# booz_main.net
KiCad netlist of a schematic drawn in EAGLE
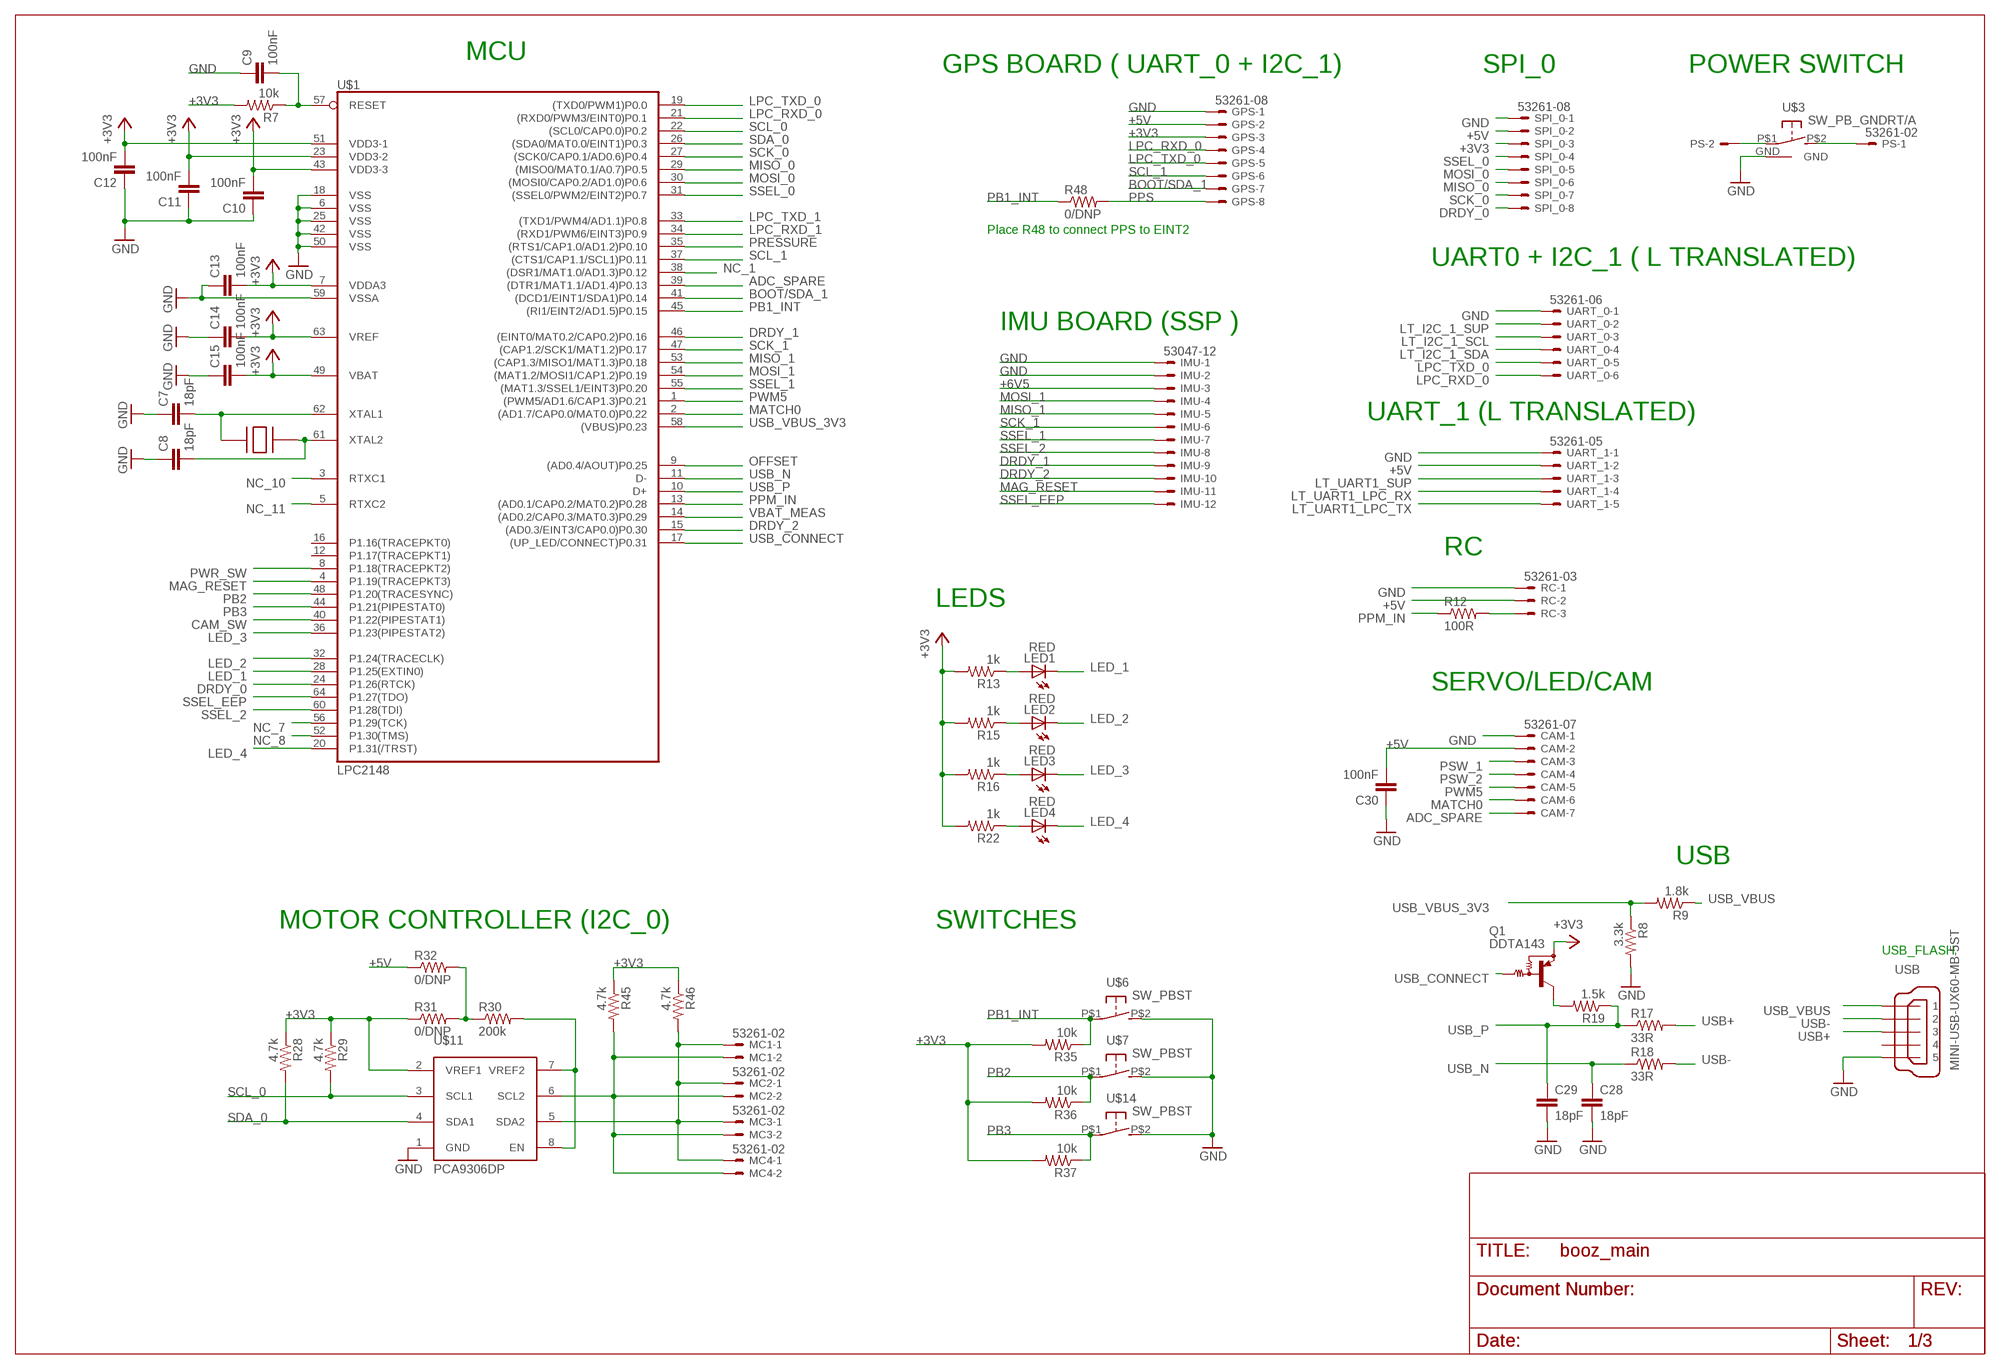
[diagram p0: schematic, sheet 1]
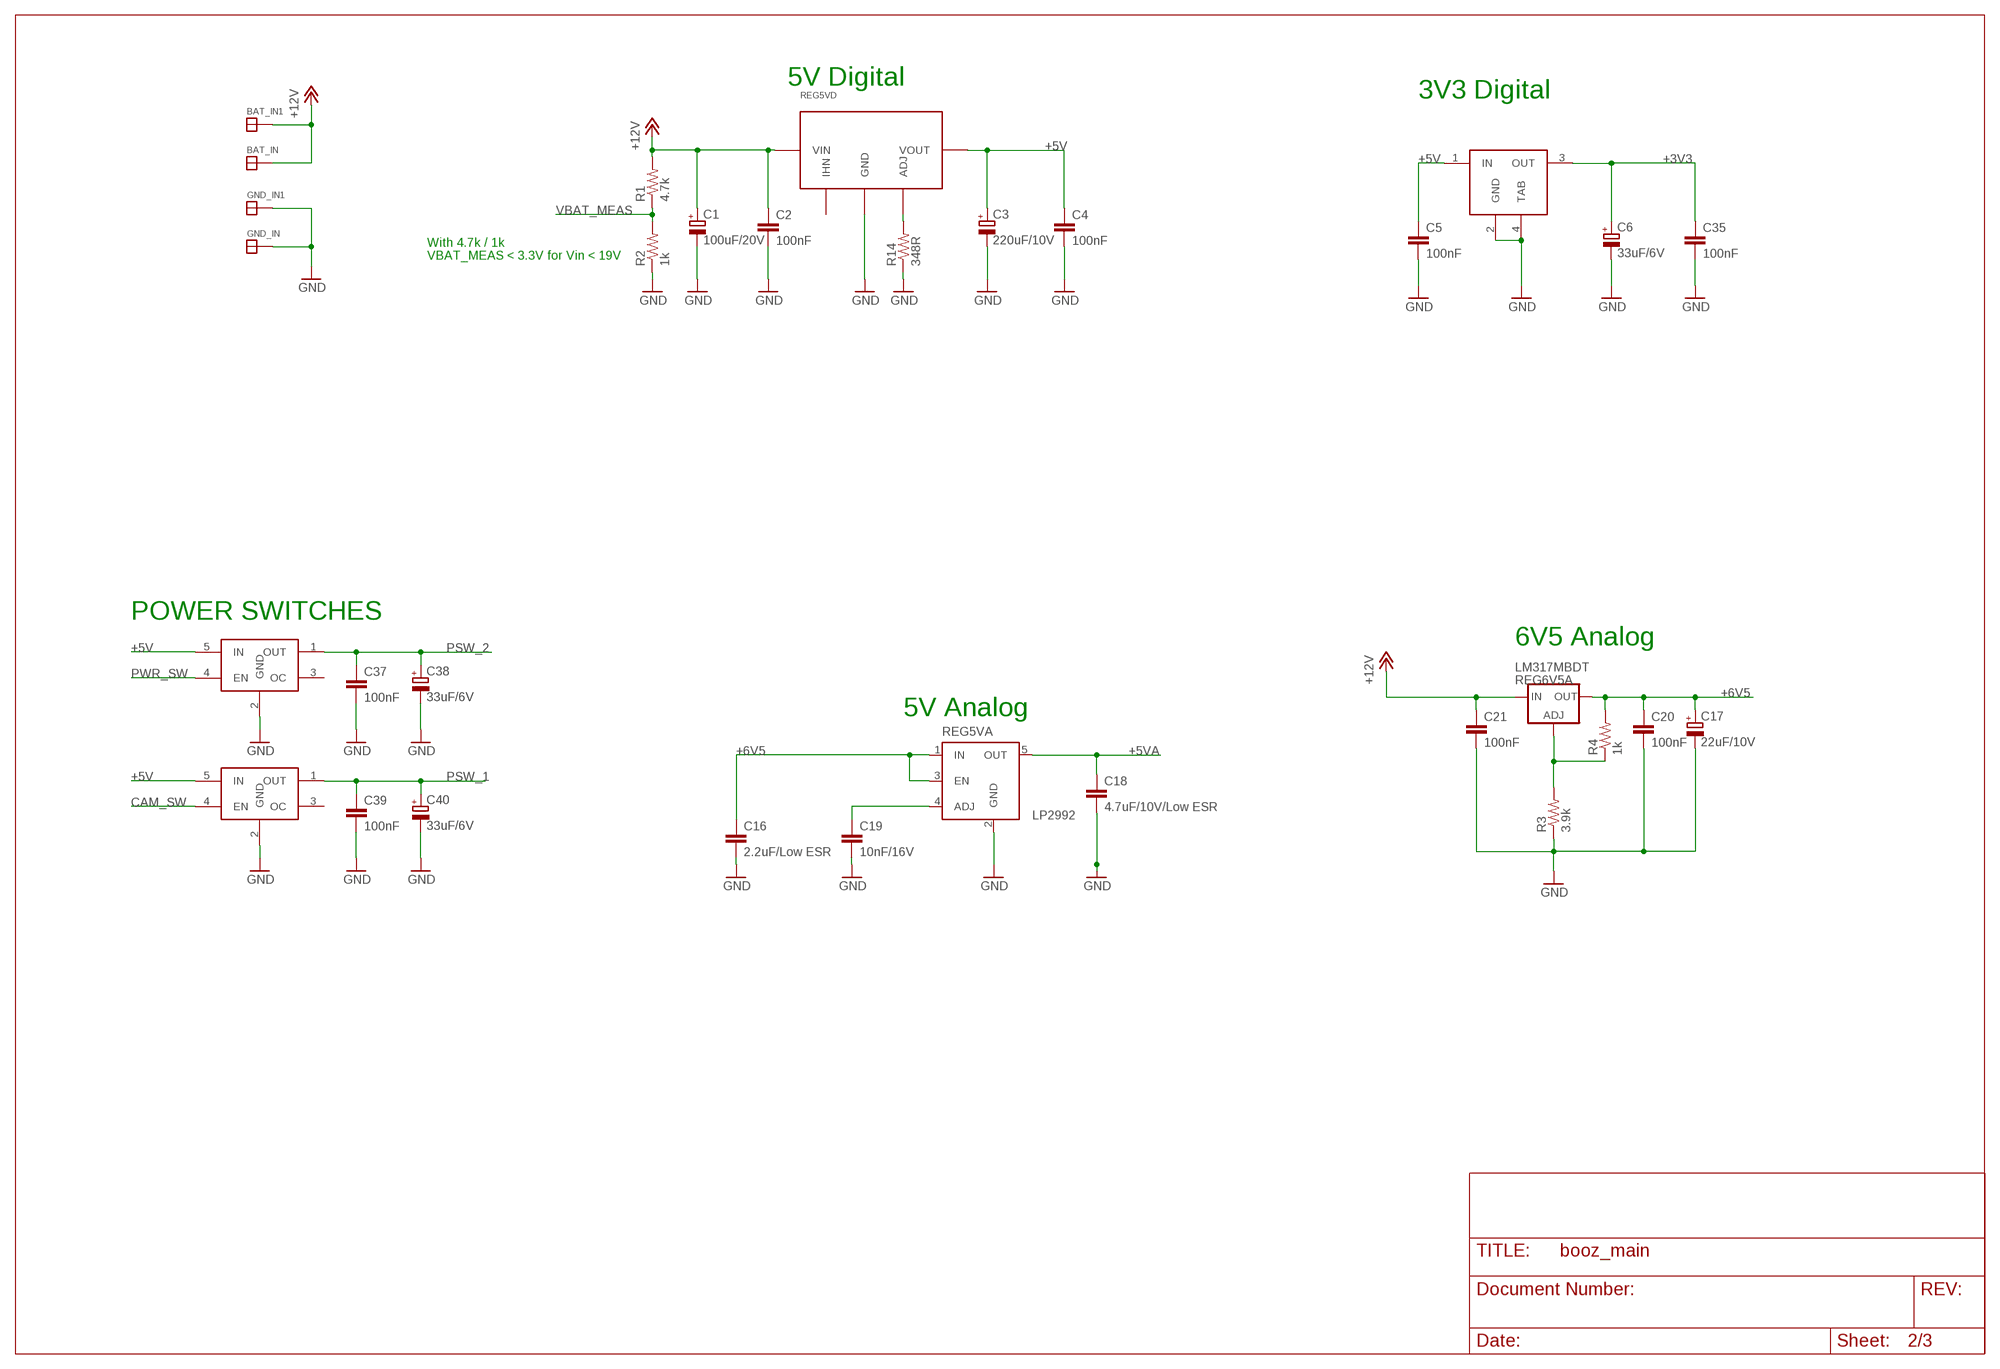
[diagram p1: schematic, sheet 2]
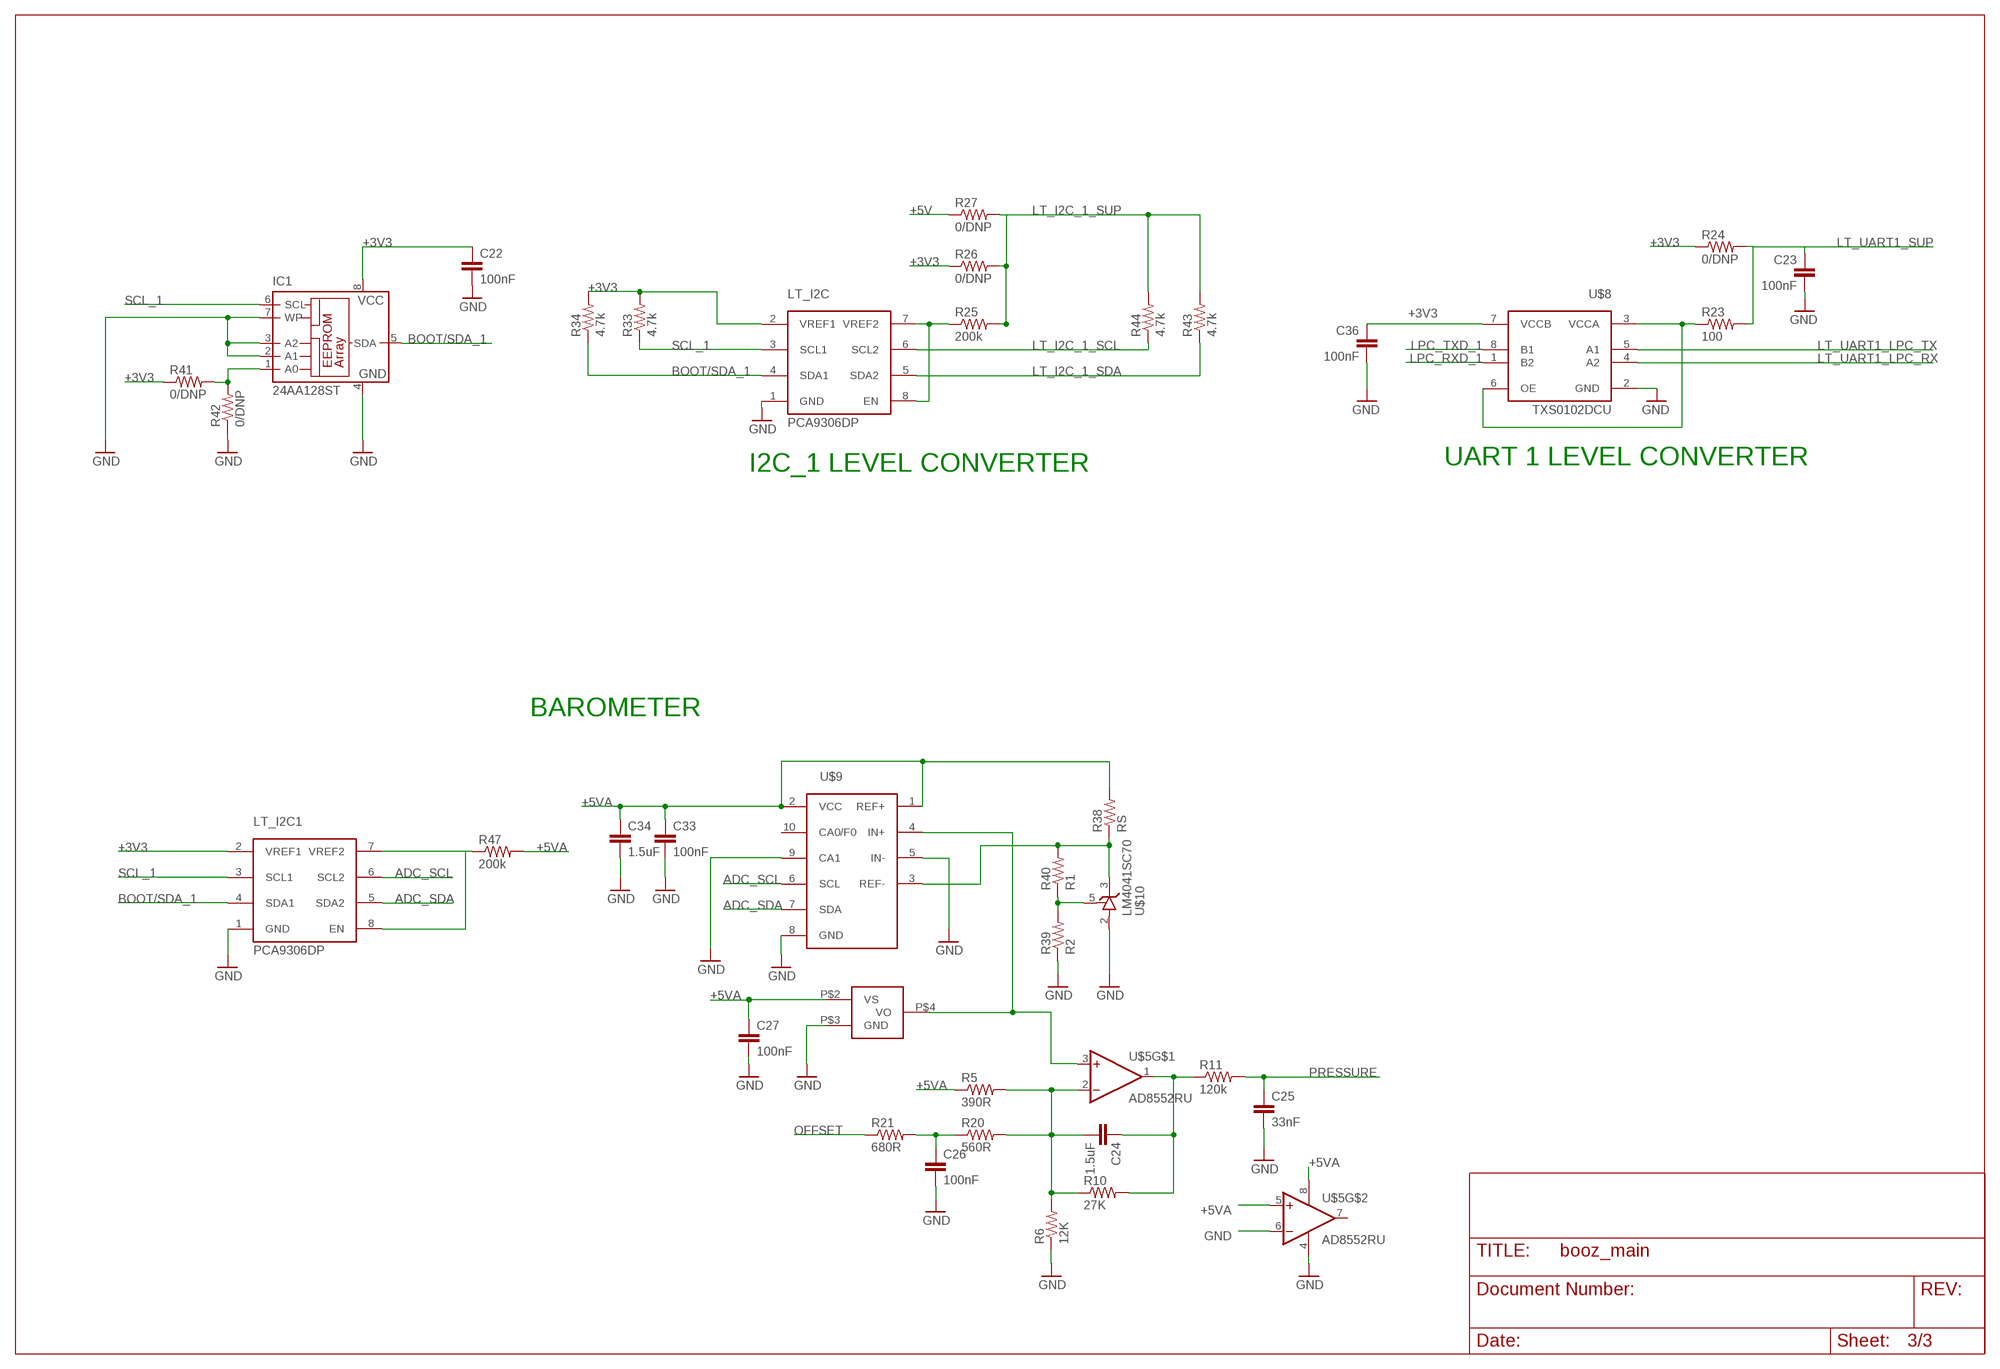
[diagram p2: schematic, sheet 3]

(export (version "E")
  (design (tool "Eeschema 10.0.6"))
  (components
    (comp (ref "C22")
      (value "100nF")
      (footprint "eagle-import:C0603")
      (libsource (lib "eagle-import") (part "C-EUC0603"))
    )
    (comp (ref "C23")
      (value "100nF")
      (footprint "eagle-import:C0603")
      (libsource (lib "eagle-import") (part "C-EUC0603"))
    )
    (comp (ref "C24")
      (value "1.5uF")
      (footprint "eagle-import:C0805")
      (libsource (lib "eagle-import") (part "C-EUC0805"))
    )
    (comp (ref "C25")
      (value "33nF")
      (footprint "eagle-import:C0805K")
      (libsource (lib "eagle-import") (part "C-EUC0805K"))
    )
    (comp (ref "C26")
      (value "100nF")
      (footprint "eagle-import:C0603")
      (libsource (lib "eagle-import") (part "C-EUC0603"))
    )
    (comp (ref "C27")
      (value "100nF")
      (footprint "eagle-import:C0603")
      (libsource (lib "eagle-import") (part "C-EUC0603"))
    )
    (comp (ref "C33")
      (value "100nF")
      (footprint "eagle-import:C0603")
      (libsource (lib "eagle-import") (part "C-EUC0603"))
    )
    (comp (ref "C34")
      (value "1.5uF")
      (footprint "eagle-import:C0805")
      (libsource (lib "eagle-import") (part "C-EUC0805"))
    )
    (comp (ref "C36")
      (value "100nF")
      (footprint "eagle-import:C0603")
      (libsource (lib "eagle-import") (part "C-EUC0603"))
    )
    (comp (ref "IC1")
      (value "24AA128ST")
      (footprint "eagle-import:TSSOP8")
      (libsource (lib "eagle-import") (part "24STAA128"))
    )
    (comp (ref "LT_I2C")
      (value "PCA9306DP")
      (footprint "eagle-import:TSSOP_B3")
      (libsource (lib "eagle-import") (part "PCA9306DP"))
    )
    (comp (ref "LT_I2C1")
      (value "PCA9306DP")
      (footprint "eagle-import:TSSOP_B3")
      (libsource (lib "eagle-import") (part "PCA9306DP"))
    )
    (comp (ref "R5")
      (value "390R")
      (footprint "eagle-import:R0603")
      (libsource (lib "eagle-import") (part "R-US_R0603"))
    )
    (comp (ref "R6")
      (value "12K")
      (footprint "eagle-import:R0603")
      (libsource (lib "eagle-import") (part "R-US_R0603"))
    )
    (comp (ref "R10")
      (value "27K")
      (footprint "eagle-import:R0603")
      (libsource (lib "eagle-import") (part "R-US_R0603"))
    )
    (comp (ref "R11")
      (value "120k")
      (footprint "eagle-import:R0603")
      (libsource (lib "eagle-import") (part "R-US_R0603"))
    )
    (comp (ref "R20")
      (value "560R")
      (footprint "eagle-import:R0603")
      (libsource (lib "eagle-import") (part "R-US_R0603"))
    )
    (comp (ref "R21")
      (value "680R")
      (footprint "eagle-import:R0603")
      (libsource (lib "eagle-import") (part "R-US_R0603"))
    )
    (comp (ref "R23")
      (value "100")
      (footprint "eagle-import:R0603")
      (libsource (lib "eagle-import") (part "R-US_R0603"))
    )
    (comp (ref "R24")
      (value "0/DNP")
      (footprint "eagle-import:R0603")
      (libsource (lib "eagle-import") (part "R-US_R0603"))
    )
    (comp (ref "R25")
      (value "200k")
      (footprint "eagle-import:R0603")
      (libsource (lib "eagle-import") (part "R-US_R0603"))
    )
    (comp (ref "R26")
      (value "0/DNP")
      (footprint "eagle-import:R0603")
      (libsource (lib "eagle-import") (part "R-US_R0603"))
    )
    (comp (ref "R27")
      (value "0/DNP")
      (footprint "eagle-import:R0603")
      (libsource (lib "eagle-import") (part "R-US_R0603"))
    )
    (comp (ref "R33")
      (value "4.7k")
      (footprint "eagle-import:R0603")
      (libsource (lib "eagle-import") (part "R-US_R0603"))
    )
    (comp (ref "R34")
      (value "4.7k")
      (footprint "eagle-import:R0603")
      (libsource (lib "eagle-import") (part "R-US_R0603"))
    )
    (comp (ref "R38")
      (value "RS")
      (footprint "eagle-import:R0603")
      (libsource (lib "eagle-import") (part "R-US_R0603"))
    )
    (comp (ref "R39")
      (value "R2")
      (footprint "eagle-import:R0603")
      (libsource (lib "eagle-import") (part "R-US_R0603"))
    )
    (comp (ref "R40")
      (value "R1")
      (footprint "eagle-import:R0603")
      (libsource (lib "eagle-import") (part "R-US_R0603"))
    )
    (comp (ref "R41")
      (value "0/DNP")
      (footprint "eagle-import:R0603")
      (libsource (lib "eagle-import") (part "R-US_R0603"))
    )
    (comp (ref "R42")
      (value "0/DNP")
      (footprint "eagle-import:R0603")
      (libsource (lib "eagle-import") (part "R-US_R0603"))
    )
    (comp (ref "R43")
      (value "4.7k")
      (footprint "eagle-import:R0603")
      (libsource (lib "eagle-import") (part "R-US_R0603"))
    )
    (comp (ref "R44")
      (value "4.7k")
      (footprint "eagle-import:R0603")
      (libsource (lib "eagle-import") (part "R-US_R0603"))
    )
    (comp (ref "R47")
      (value "200k")
      (footprint "eagle-import:R0603")
      (libsource (lib "eagle-import") (part "R-US_R0603"))
    )
    (comp (ref "U$2")
      (value "MPX6115")
      (footprint "eagle-import:CASE_1317")
      (libsource (lib "eagle-import") (part "MPX6115"))
    )
    (comp (ref "U$5")
      (value "AD8552RU")
      (footprint "eagle-import:TSSOP8")
      (libsource (lib "eagle-import") (part "AD8552RU"))
    )
    (comp (ref "U$8")
      (value "TXS0102DCU")
      (footprint "eagle-import:US8")
      (libsource (lib "eagle-import") (part "TXS0102DCU"))
    )
    (comp (ref "U$9")
      (value "LTC2485")
      (footprint "eagle-import:DFN10")
      (libsource (lib "eagle-import") (part "LTC2485"))
    )
    (comp (ref "U$10")
      (value "LM4041SC70")
      (footprint "eagle-import:SC70-5L")
      (libsource (lib "eagle-import") (part "LM4041SC70"))
    )
    (comp (ref "C7")
      (value "18pF")
      (footprint "eagle-import:C0603")
      (libsource (lib "eagle-import") (part "C-EUC0603"))
    )
    (comp (ref "C8")
      (value "18pF")
      (footprint "eagle-import:C0603")
      (libsource (lib "eagle-import") (part "C-EUC0603"))
    )
    (comp (ref "C9")
      (value "100nF")
      (footprint "eagle-import:C0603")
      (libsource (lib "eagle-import") (part "C-EUC0603"))
    )
    (comp (ref "C10")
      (value "100nF")
      (footprint "eagle-import:C0603")
      (libsource (lib "eagle-import") (part "C-EUC0603"))
    )
    (comp (ref "C11")
      (value "100nF")
      (footprint "eagle-import:C0603")
      (libsource (lib "eagle-import") (part "C-EUC0603"))
    )
    (comp (ref "C12")
      (value "100nF")
      (footprint "eagle-import:C0603")
      (libsource (lib "eagle-import") (part "C-EUC0603"))
    )
    (comp (ref "C13")
      (value "100nF")
      (footprint "eagle-import:C0603")
      (libsource (lib "eagle-import") (part "C-EUC0603"))
    )
    (comp (ref "C14")
      (value "100nF")
      (footprint "eagle-import:C0603")
      (libsource (lib "eagle-import") (part "C-EUC0603"))
    )
    (comp (ref "C15")
      (value "100nF")
      (footprint "eagle-import:C0603")
      (libsource (lib "eagle-import") (part "C-EUC0603"))
    )
    (comp (ref "C28")
      (value "18pF")
      (footprint "eagle-import:C0603")
      (libsource (lib "eagle-import") (part "C-EUC0603"))
    )
    (comp (ref "C29")
      (value "18pF")
      (footprint "eagle-import:C0603")
      (libsource (lib "eagle-import") (part "C-EUC0603"))
    )
    (comp (ref "C30")
      (value "100nF")
      (footprint "eagle-import:C0603")
      (libsource (lib "eagle-import") (part "C-EUC0603"))
    )
    (comp (ref "CAM")
      (value "53261-07")
      (footprint "eagle-import:53261-07")
      (libsource (lib "eagle-import") (part "53?-07261"))
    )
    (comp (ref "GPS")
      (value "53261-08")
      (footprint "eagle-import:53261-08")
      (libsource (lib "eagle-import") (part "53?-08261"))
    )
    (comp (ref "IMU")
      (value "53047-12")
      (footprint "eagle-import:53047-12")
      (libsource (lib "eagle-import") (part "53?-12047"))
    )
    (comp (ref "LED1")
      (value "RED")
      (footprint "eagle-import:CHIP-LED0805")
      (libsource (lib "eagle-import") (part "LEDCHIP-LED0805"))
    )
    (comp (ref "LED2")
      (value "RED")
      (footprint "eagle-import:CHIP-LED0805")
      (libsource (lib "eagle-import") (part "LEDCHIP-LED0805"))
    )
    (comp (ref "LED3")
      (value "RED")
      (footprint "eagle-import:CHIP-LED0805")
      (libsource (lib "eagle-import") (part "LEDCHIP-LED0805"))
    )
    (comp (ref "LED4")
      (value "RED")
      (footprint "eagle-import:CHIP-LED0805")
      (libsource (lib "eagle-import") (part "LEDCHIP-LED0805"))
    )
    (comp (ref "MC1")
      (value "53261-02")
      (footprint "eagle-import:53261-02")
      (libsource (lib "eagle-import") (part "53?-02261"))
    )
    (comp (ref "MC2")
      (value "53261-02")
      (footprint "eagle-import:53261-02")
      (libsource (lib "eagle-import") (part "53?-02261"))
    )
    (comp (ref "MC3")
      (value "53261-02")
      (footprint "eagle-import:53261-02")
      (libsource (lib "eagle-import") (part "53?-02261"))
    )
    (comp (ref "MC4")
      (value "53261-02")
      (footprint "eagle-import:53261-02")
      (libsource (lib "eagle-import") (part "53?-02261"))
    )
    (comp (ref "PS")
      (value "53261-02")
      (footprint "eagle-import:53261-02")
      (libsource (lib "eagle-import") (part "53?-02261"))
    )
    (comp (ref "Q1")
      (value "DDTA143")
      (footprint "eagle-import:SC59-BEC")
      (libsource (lib "eagle-import") (part "MUN2111T1"))
    )
    (comp (ref "R7")
      (value "10k")
      (footprint "eagle-import:R0603")
      (libsource (lib "eagle-import") (part "R-US_R0603"))
    )
    (comp (ref "R8")
      (value "3.3k")
      (footprint "eagle-import:R0603")
      (libsource (lib "eagle-import") (part "R-US_R0603"))
    )
    (comp (ref "R9")
      (value "1.8k")
      (footprint "eagle-import:R0603")
      (libsource (lib "eagle-import") (part "R-US_R0603"))
    )
    (comp (ref "R12")
      (value "100R")
      (footprint "eagle-import:R0603")
      (libsource (lib "eagle-import") (part "R-US_R0603"))
    )
    (comp (ref "R13")
      (value "1k")
      (footprint "eagle-import:R0603")
      (libsource (lib "eagle-import") (part "R-US_R0603"))
    )
    (comp (ref "R15")
      (value "1k")
      (footprint "eagle-import:R0603")
      (libsource (lib "eagle-import") (part "R-US_R0603"))
    )
    (comp (ref "R16")
      (value "1k")
      (footprint "eagle-import:R0603")
      (libsource (lib "eagle-import") (part "R-US_R0603"))
    )
    (comp (ref "R17")
      (value "33R")
      (footprint "eagle-import:R0603")
      (libsource (lib "eagle-import") (part "R-US_R0603"))
    )
    (comp (ref "R18")
      (value "33R")
      (footprint "eagle-import:R0603")
      (libsource (lib "eagle-import") (part "R-US_R0603"))
    )
    (comp (ref "R19")
      (value "1.5k")
      (footprint "eagle-import:R0603")
      (libsource (lib "eagle-import") (part "R-US_R0603"))
    )
    (comp (ref "R22")
      (value "1k")
      (footprint "eagle-import:R0603")
      (libsource (lib "eagle-import") (part "R-US_R0603"))
    )
    (comp (ref "R28")
      (value "4.7k")
      (footprint "eagle-import:R0603")
      (libsource (lib "eagle-import") (part "R-US_R0603"))
    )
    (comp (ref "R29")
      (value "4.7k")
      (footprint "eagle-import:R0603")
      (libsource (lib "eagle-import") (part "R-US_R0603"))
    )
    (comp (ref "R30")
      (value "200k")
      (footprint "eagle-import:R0603")
      (libsource (lib "eagle-import") (part "R-US_R0603"))
    )
    (comp (ref "R31")
      (value "0/DNP")
      (footprint "eagle-import:R0603")
      (libsource (lib "eagle-import") (part "R-US_R0603"))
    )
    (comp (ref "R32")
      (value "0/DNP")
      (footprint "eagle-import:R0603")
      (libsource (lib "eagle-import") (part "R-US_R0603"))
    )
    (comp (ref "R35")
      (value "10k")
      (footprint "eagle-import:R0603")
      (libsource (lib "eagle-import") (part "R-US_R0603"))
    )
    (comp (ref "R36")
      (value "10k")
      (footprint "eagle-import:R0603")
      (libsource (lib "eagle-import") (part "R-US_R0603"))
    )
    (comp (ref "R37")
      (value "10k")
      (footprint "eagle-import:R0603")
      (libsource (lib "eagle-import") (part "R-US_R0603"))
    )
    (comp (ref "R45")
      (value "4.7k")
      (footprint "eagle-import:R0603")
      (libsource (lib "eagle-import") (part "R-US_R0603"))
    )
    (comp (ref "R46")
      (value "4.7k")
      (footprint "eagle-import:R0603")
      (libsource (lib "eagle-import") (part "R-US_R0603"))
    )
    (comp (ref "R48")
      (value "0/DNP")
      (footprint "eagle-import:R0603")
      (libsource (lib "eagle-import") (part "R-US_R0603"))
    )
    (comp (ref "RC")
      (value "53261-03")
      (footprint "eagle-import:53261-03")
      (libsource (lib "eagle-import") (part "53?-03261"))
    )
    (comp (ref "SPI_0")
      (value "53261-08")
      (footprint "eagle-import:53261-08")
      (libsource (lib "eagle-import") (part "53?-08261"))
    )
    (comp (ref "U$1")
      (value "LPC2148")
      (footprint "eagle-import:SQFP-S-10X10-64")
      (libsource (lib "eagle-import") (part "LPC2148"))
    )
    (comp (ref "U$3")
      (value "SW_PB_GNDRT/A")
      (footprint "eagle-import:B3U-3100P")
      (libsource (lib "eagle-import") (part "SW_PB_GNDRT/A"))
    )
    (comp (ref "U$4")
      (value "CRYSTAL_CTS")
      (footprint "eagle-import:CTS_CRYSTAL")
      (libsource (lib "eagle-import") (part "CRYSTAL_CTS"))
    )
    (comp (ref "U$6")
      (value "SW_PBST")
      (footprint "eagle-import:B3U-1000P")
      (libsource (lib "eagle-import") (part "SW_PBST"))
    )
    (comp (ref "U$7")
      (value "SW_PBST")
      (footprint "eagle-import:B3U-1000P")
      (libsource (lib "eagle-import") (part "SW_PBST"))
    )
    (comp (ref "U$11")
      (value "PCA9306DP")
      (footprint "eagle-import:TSSOP_B3")
      (libsource (lib "eagle-import") (part "PCA9306DP"))
    )
    (comp (ref "U$14")
      (value "SW_PBST")
      (footprint "eagle-import:B3U-1000P")
      (libsource (lib "eagle-import") (part "SW_PBST"))
    )
    (comp (ref "UART_0")
      (value "53261-06")
      (footprint "eagle-import:53261-06")
      (libsource (lib "eagle-import") (part "53?-06261"))
    )
    (comp (ref "UART_1")
      (value "53261-05")
      (footprint "eagle-import:53261-05")
      (libsource (lib "eagle-import") (part "53?-05261"))
    )
    (comp (ref "USB")
      (value "MINI-USB-UX60-MB-5ST")
      (footprint "eagle-import:UX60-MB-5ST")
      (libsource (lib "eagle-import") (part "MINI-USB-UX60-MB-5ST"))
    )
    (comp (ref "BAT_IN")
      (value "SOLDER_PAD150_75")
      (footprint "eagle-import:SOLD_PAD_150_75")
      (libsource (lib "eagle-import") (part "SOLDER_PAD150_75"))
    )
    (comp (ref "BAT_IN1")
      (value "SOLDER_PAD150_75")
      (footprint "eagle-import:SOLD_PAD_150_75")
      (libsource (lib "eagle-import") (part "SOLDER_PAD150_75"))
    )
    (comp (ref "C1")
      (value "100uF/20V")
      (footprint "eagle-import:SMC_D")
      (libsource (lib "eagle-import") (part "CPOL-EUSMCD"))
    )
    (comp (ref "C2")
      (value "100nF")
      (footprint "eagle-import:C0603")
      (libsource (lib "eagle-import") (part "C-EUC0603"))
    )
    (comp (ref "C3")
      (value "220uF/10V")
      (footprint "eagle-import:SMC_D")
      (libsource (lib "eagle-import") (part "CPOL-EUSMCD"))
    )
    (comp (ref "C4")
      (value "100nF")
      (footprint "eagle-import:C0603")
      (libsource (lib "eagle-import") (part "C-EUC0603"))
    )
    (comp (ref "C5")
      (value "100nF")
      (footprint "eagle-import:C0603")
      (libsource (lib "eagle-import") (part "C-EUC0603"))
    )
    (comp (ref "C6")
      (value "33uF/6V")
      (footprint "eagle-import:CT3216")
      (libsource (lib "eagle-import") (part "CPOL-EUCT3216"))
    )
    (comp (ref "C16")
      (value "2.2uF/Low ESR")
      (footprint "eagle-import:C0603")
      (libsource (lib "eagle-import") (part "C-EUC0603"))
    )
    (comp (ref "C17")
      (value "22uF/10V")
      (footprint "eagle-import:CT3216")
      (libsource (lib "eagle-import") (part "CPOL-EUCT3216"))
    )
    (comp (ref "C18")
      (value "4.7uF/10V/Low ESR")
      (footprint "eagle-import:C0805K")
      (libsource (lib "eagle-import") (part "C-EUC0805K"))
    )
    (comp (ref "C19")
      (value "10nF/16V")
      (footprint "eagle-import:C0603K")
      (libsource (lib "eagle-import") (part "C-EUC0603K"))
    )
    (comp (ref "C20")
      (value "100nF")
      (footprint "eagle-import:C0603")
      (libsource (lib "eagle-import") (part "C-EUC0603"))
    )
    (comp (ref "C21")
      (value "100nF")
      (footprint "eagle-import:C0603")
      (libsource (lib "eagle-import") (part "C-EUC0603"))
    )
    (comp (ref "C35")
      (value "100nF")
      (footprint "eagle-import:C0603")
      (libsource (lib "eagle-import") (part "C-EUC0603"))
    )
    (comp (ref "C37")
      (value "100nF")
      (footprint "eagle-import:C0603")
      (libsource (lib "eagle-import") (part "C-EUC0603"))
    )
    (comp (ref "C38")
      (value "33uF/6V")
      (footprint "eagle-import:CT3216")
      (libsource (lib "eagle-import") (part "CPOL-EUCT3216"))
    )
    (comp (ref "C39")
      (value "100nF")
      (footprint "eagle-import:C0603")
      (libsource (lib "eagle-import") (part "C-EUC0603"))
    )
    (comp (ref "C40")
      (value "33uF/6V")
      (footprint "eagle-import:CT3216")
      (libsource (lib "eagle-import") (part "CPOL-EUCT3216"))
    )
    (comp (ref "GND_IN")
      (value "SOLDER_PAD150_75")
      (footprint "eagle-import:SOLD_PAD_150_75")
      (libsource (lib "eagle-import") (part "SOLDER_PAD150_75"))
    )
    (comp (ref "GND_IN1")
      (value "SOLDER_PAD150_75")
      (footprint "eagle-import:SOLD_PAD_150_75")
      (libsource (lib "eagle-import") (part "SOLDER_PAD150_75"))
    )
    (comp (ref "R1")
      (value "4.7k")
      (footprint "eagle-import:R0603")
      (libsource (lib "eagle-import") (part "R-US_R0603"))
    )
    (comp (ref "R2")
      (value "1k")
      (footprint "eagle-import:R0603")
      (libsource (lib "eagle-import") (part "R-US_R0603"))
    )
    (comp (ref "R3")
      (value "3.9k")
      (footprint "eagle-import:R0603")
      (libsource (lib "eagle-import") (part "R-US_R0603"))
    )
    (comp (ref "R4")
      (value "1k")
      (footprint "eagle-import:R0603")
      (libsource (lib "eagle-import") (part "R-US_R0603"))
    )
    (comp (ref "R14")
      (value "348R")
      (footprint "eagle-import:R0603")
      (libsource (lib "eagle-import") (part "R-US_R0603"))
    )
    (comp (ref "REG3V3D")
      (value "LM3940IMP-3.3")
      (footprint "eagle-import:SOT223-R")
      (libsource (lib "eagle-import") (part "LM3940IMP-3.3"))
    )
    (comp (ref "REG5VA")
      (value "LP2992")
      (footprint "eagle-import:SOT23-5")
      (libsource (lib "eagle-import") (part "MIC5219BM5"))
    )
    (comp (ref "REG5VD")
      (value "PTHTH")
      (footprint "eagle-import:PTH_TH")
      (libsource (lib "eagle-import") (part "PTHTH"))
    )
    (comp (ref "REG6V5A")
      (value "LM317MBDT")
      (footprint "eagle-import:DPACK")
      (libsource (lib "eagle-import") (part "LM317?MBDT"))
    )
    (comp (ref "U$12")
      (value "TPS2051B")
      (footprint "eagle-import:SOT23-5L")
      (libsource (lib "eagle-import") (part "TPS2051B"))
    )
    (comp (ref "U$13")
      (value "TPS2051B")
      (footprint "eagle-import:SOT23-5L")
      (libsource (lib "eagle-import") (part "TPS2051B"))
    )
  )
  (nets
    (net (code "1") (name "+3V3") (class "Default")
      (node (ref "C10") (pin "2") (pinfunction "2_2") (pintype "passive"))
      (node (ref "C11") (pin "2") (pinfunction "2_2") (pintype "passive"))
      (node (ref "C12") (pin "2") (pinfunction "2_2") (pintype "passive"))
      (node (ref "C13") (pin "2") (pinfunction "2_2") (pintype "passive"))
      (node (ref "C14") (pin "2") (pinfunction "2_2") (pintype "passive"))
      (node (ref "C15") (pin "2") (pinfunction "2_2") (pintype "passive"))
      (node (ref "C22") (pin "1") (pinfunction "1_1") (pintype "passive"))
      (node (ref "C35") (pin "1") (pinfunction "1_1") (pintype "passive"))
      (node (ref "C36") (pin "1") (pinfunction "1_1") (pintype "passive"))
      (node (ref "C6") (pin "+") (pinfunction "+_+") (pintype "passive"))
      (node (ref "GPS") (pin "3") (pinfunction "S_3") (pintype "passive"))
      (node (ref "IC1") (pin "8") (pinfunction "VCC_8") (pintype "power_in"))
      (node (ref "LT_I2C") (pin "2") (pinfunction "VREF1_2") (pintype "bidirectional"))
      (node (ref "LT_I2C1") (pin "2") (pinfunction "VREF1_2") (pintype "bidirectional"))
      (node (ref "Q1") (pin "E") (pinfunction "E_E") (pintype "passive"))
      (node (ref "R13") (pin "2") (pinfunction "2_2") (pintype "passive"))
      (node (ref "R15") (pin "2") (pinfunction "2_2") (pintype "passive"))
      (node (ref "R16") (pin "2") (pinfunction "2_2") (pintype "passive"))
      (node (ref "R22") (pin "2") (pinfunction "2_2") (pintype "passive"))
      (node (ref "R24") (pin "1") (pinfunction "1_1") (pintype "passive"))
      (node (ref "R26") (pin "1") (pinfunction "1_1") (pintype "passive"))
      (node (ref "R28") (pin "1") (pinfunction "1_1") (pintype "passive"))
      (node (ref "R29") (pin "1") (pinfunction "1_1") (pintype "passive"))
      (node (ref "R31") (pin "1") (pinfunction "1_1") (pintype "passive"))
      (node (ref "R33") (pin "2") (pinfunction "2_2") (pintype "passive"))
      (node (ref "R34") (pin "2") (pinfunction "2_2") (pintype "passive"))
      (node (ref "R35") (pin "2") (pinfunction "2_2") (pintype "passive"))
      (node (ref "R36") (pin "2") (pinfunction "2_2") (pintype "passive"))
      (node (ref "R37") (pin "2") (pinfunction "2_2") (pintype "passive"))
      (node (ref "R41") (pin "1") (pinfunction "1_1") (pintype "passive"))
      (node (ref "R45") (pin "1") (pinfunction "1_1") (pintype "passive"))
      (node (ref "R46") (pin "1") (pinfunction "1_1") (pintype "passive"))
      (node (ref "R7") (pin "2") (pinfunction "2_2") (pintype "passive"))
      (node (ref "REG3V3D") (pin "3") (pinfunction "OUT_3") (pintype "bidirectional"))
      (node (ref "SPI_0") (pin "3") (pinfunction "S_3") (pintype "passive"))
      (node (ref "U$1") (pin "23") (pinfunction "VDD3-2_23") (pintype "power_in"))
      (node (ref "U$1") (pin "43") (pinfunction "VDD3-3_43") (pintype "power_in"))
      (node (ref "U$1") (pin "49") (pinfunction "VBAT_49") (pintype "power_in"))
      (node (ref "U$1") (pin "51") (pinfunction "VDD3-1_51") (pintype "power_in"))
      (node (ref "U$1") (pin "63") (pinfunction "VREF_63") (pintype "input"))
      (node (ref "U$1") (pin "7") (pinfunction "VDDA3_7") (pintype "power_in"))
      (node (ref "U$11") (pin "2") (pinfunction "VREF1_2") (pintype "bidirectional"))
      (node (ref "U$8") (pin "7") (pinfunction "VCCB_7") (pintype "bidirectional"))
    )
    (net (code "2") (name "+5V") (class "Default")
      (node (ref "C3") (pin "+") (pinfunction "+_+") (pintype "passive"))
      (node (ref "C30") (pin "2") (pinfunction "2_2") (pintype "passive"))
      (node (ref "C4") (pin "1") (pinfunction "1_1") (pintype "passive"))
      (node (ref "C5") (pin "1") (pinfunction "1_1") (pintype "passive"))
      (node (ref "CAM") (pin "2") (pinfunction "S_2") (pintype "passive"))
      (node (ref "GPS") (pin "2") (pinfunction "S_2") (pintype "passive"))
      (node (ref "R27") (pin "1") (pinfunction "1_1") (pintype "passive"))
      (node (ref "R32") (pin "1") (pinfunction "1_1") (pintype "passive"))
      (node (ref "RC") (pin "2") (pinfunction "S_2") (pintype "passive"))
      (node (ref "REG3V3D") (pin "1") (pinfunction "IN_1") (pintype "bidirectional"))
      (node (ref "REG5VD") (pin "P$3") (pinfunction "VOUT_P$3") (pintype "bidirectional"))
      (node (ref "SPI_0") (pin "2") (pinfunction "S_2") (pintype "passive"))
      (node (ref "U$12") (pin "5") (pinfunction "IN_5") (pintype "bidirectional"))
      (node (ref "U$13") (pin "5") (pinfunction "IN_5") (pintype "bidirectional"))
      (node (ref "UART_1") (pin "2") (pinfunction "S_2") (pintype "passive"))
    )
    (net (code "3") (name "+5VA") (class "Default")
      (node (ref "C18") (pin "1") (pinfunction "1_1") (pintype "passive"))
      (node (ref "C27") (pin "1") (pinfunction "1_1") (pintype "passive"))
      (node (ref "C33") (pin "1") (pinfunction "1_1") (pintype "passive"))
      (node (ref "C34") (pin "1") (pinfunction "1_1") (pintype "passive"))
      (node (ref "R38") (pin "2") (pinfunction "2_2") (pintype "passive"))
      (node (ref "R47") (pin "2") (pinfunction "2_2") (pintype "passive"))
      (node (ref "R5") (pin "1") (pinfunction "1_1") (pintype "passive"))
      (node (ref "REG5VA") (pin "5") (pinfunction "OUT_5") (pintype "output"))
      (node (ref "U$2") (pin "P$2") (pinfunction "VS_P$2") (pintype "bidirectional"))
      (node (ref "U$5") (pin "5") (pinfunction "+IN_5") (pintype "input"))
      (node (ref "U$5") (pin "8") (pinfunction "V+_8") (pintype "power_in"))
      (node (ref "U$9") (pin "1") (pinfunction "REF+_1") (pintype "bidirectional"))
      (node (ref "U$9") (pin "2") (pinfunction "VCC_2") (pintype "bidirectional"))
    )
    (net (code "4") (name "+6V5") (class "Default")
      (node (ref "C16") (pin "1") (pinfunction "1_1") (pintype "passive"))
      (node (ref "C17") (pin "+") (pinfunction "+_+") (pintype "passive"))
      (node (ref "C20") (pin "1") (pinfunction "1_1") (pintype "passive"))
      (node (ref "IMU") (pin "3") (pinfunction "S_3") (pintype "passive"))
      (node (ref "R4") (pin "2") (pinfunction "2_2") (pintype "passive"))
      (node (ref "REG5VA") (pin "1") (pinfunction "IN_1") (pintype "input"))
      (node (ref "REG5VA") (pin "3") (pinfunction "EN_3") (pintype "input"))
      (node (ref "REG6V5A") (pin "4") (pinfunction "OUT_4") (pintype "passive"))
    )
    (net (code "5") (name "+12V") (class "Default")
      (node (ref "BAT_IN") (pin "P$1") (pinfunction "P$1_P$1") (pintype "bidirectional"))
      (node (ref "BAT_IN1") (pin "P$1") (pinfunction "P$1_P$1") (pintype "bidirectional"))
      (node (ref "C1") (pin "+") (pinfunction "+_+") (pintype "passive"))
      (node (ref "C2") (pin "1") (pinfunction "1_1") (pintype "passive"))
      (node (ref "C21") (pin "1") (pinfunction "1_1") (pintype "passive"))
      (node (ref "R1") (pin "2") (pinfunction "2_2") (pintype "passive"))
      (node (ref "REG5VD") (pin "P$1") (pinfunction "VIN_P$1") (pintype "bidirectional"))
      (node (ref "REG6V5A") (pin "3") (pinfunction "IN_3") (pintype "input"))
    )
    (net (code "6") (name "ADC_SCL") (class "Default")
      (node (ref "LT_I2C1") (pin "6") (pinfunction "SCL2_6") (pintype "bidirectional"))
      (node (ref "U$9") (pin "6") (pinfunction "SCL_6") (pintype "bidirectional"))
    )
    (net (code "7") (name "ADC_SDA") (class "Default")
      (node (ref "LT_I2C1") (pin "5") (pinfunction "SDA2_5") (pintype "bidirectional"))
      (node (ref "U$9") (pin "7") (pinfunction "SDA_7") (pintype "bidirectional"))
    )
    (net (code "8") (name "ADC_SPARE") (class "Default")
      (node (ref "CAM") (pin "7") (pinfunction "S_7") (pintype "passive"))
      (node (ref "U$1") (pin "39") (pinfunction "(DTR1/MAT1.1/AD1.4)P0.13_39") (pintype "bidirectional"))
    )
    (net (code "9") (name "BOOT{slash}SDA_1") (class "Default")
      (node (ref "GPS") (pin "7") (pinfunction "S_7") (pintype "passive"))
      (node (ref "IC1") (pin "5") (pinfunction "SDA_5") (pintype "bidirectional"))
      (node (ref "LT_I2C") (pin "4") (pinfunction "SDA1_4") (pintype "bidirectional"))
      (node (ref "LT_I2C1") (pin "4") (pinfunction "SDA1_4") (pintype "bidirectional"))
      (node (ref "R34") (pin "1") (pinfunction "1_1") (pintype "passive"))
      (node (ref "U$1") (pin "41") (pinfunction "(DCD1/EINT1/SDA1)P0.14_41") (pintype "bidirectional"))
    )
    (net (code "10") (name "CAM_SW") (class "Default")
      (node (ref "U$1") (pin "40") (pinfunction "P1.22(PIPESTAT1)_40") (pintype "bidirectional"))
      (node (ref "U$13") (pin "4") (pinfunction "EN_4") (pintype "bidirectional"))
    )
    (net (code "11") (name "DRDY_0") (class "Default")
      (node (ref "SPI_0") (pin "8") (pinfunction "S_8") (pintype "passive"))
      (node (ref "U$1") (pin "24") (pinfunction "P1.26(RTCK)_24") (pintype "bidirectional"))
    )
    (net (code "12") (name "DRDY_1") (class "Default")
      (node (ref "IMU") (pin "9") (pinfunction "S_9") (pintype "passive"))
      (node (ref "U$1") (pin "46") (pinfunction "(EINT0/MAT0.2/CAP0.2)P0.16_46") (pintype "bidirectional"))
    )
    (net (code "13") (name "DRDY_2") (class "Default")
      (node (ref "IMU") (pin "10") (pinfunction "S_10") (pintype "passive"))
      (node (ref "U$1") (pin "15") (pinfunction "(AD0.3/EINT3/CAP0.0)P0.30_15") (pintype "bidirectional"))
    )
    (net (code "14") (name "GND") (class "Default")
      (node (ref "C1") (pin "-") (pinfunction "-_-") (pintype "passive"))
      (node (ref "C10") (pin "1") (pinfunction "1_1") (pintype "passive"))
      (node (ref "C11") (pin "1") (pinfunction "1_1") (pintype "passive"))
      (node (ref "C12") (pin "1") (pinfunction "1_1") (pintype "passive"))
      (node (ref "C13") (pin "1") (pinfunction "1_1") (pintype "passive"))
      (node (ref "C14") (pin "1") (pinfunction "1_1") (pintype "passive"))
      (node (ref "C15") (pin "1") (pinfunction "1_1") (pintype "passive"))
      (node (ref "C16") (pin "2") (pinfunction "2_2") (pintype "passive"))
      (node (ref "C17") (pin "-") (pinfunction "-_-") (pintype "passive"))
      (node (ref "C18") (pin "2") (pinfunction "2_2") (pintype "passive"))
      (node (ref "C19") (pin "2") (pinfunction "2_2") (pintype "passive"))
      (node (ref "C2") (pin "2") (pinfunction "2_2") (pintype "passive"))
      (node (ref "C20") (pin "2") (pinfunction "2_2") (pintype "passive"))
      (node (ref "C21") (pin "2") (pinfunction "2_2") (pintype "passive"))
      (node (ref "C22") (pin "2") (pinfunction "2_2") (pintype "passive"))
      (node (ref "C23") (pin "2") (pinfunction "2_2") (pintype "passive"))
      (node (ref "C25") (pin "2") (pinfunction "2_2") (pintype "passive"))
      (node (ref "C26") (pin "2") (pinfunction "2_2") (pintype "passive"))
      (node (ref "C27") (pin "2") (pinfunction "2_2") (pintype "passive"))
      (node (ref "C28") (pin "2") (pinfunction "2_2") (pintype "passive"))
      (node (ref "C29") (pin "2") (pinfunction "2_2") (pintype "passive"))
      (node (ref "C3") (pin "-") (pinfunction "-_-") (pintype "passive"))
      (node (ref "C30") (pin "1") (pinfunction "1_1") (pintype "passive"))
      (node (ref "C33") (pin "2") (pinfunction "2_2") (pintype "passive"))
      (node (ref "C34") (pin "2") (pinfunction "2_2") (pintype "passive"))
      (node (ref "C35") (pin "2") (pinfunction "2_2") (pintype "passive"))
      (node (ref "C36") (pin "2") (pinfunction "2_2") (pintype "passive"))
      (node (ref "C37") (pin "2") (pinfunction "2_2") (pintype "passive"))
      (node (ref "C38") (pin "-") (pinfunction "-_-") (pintype "passive"))
      (node (ref "C39") (pin "2") (pinfunction "2_2") (pintype "passive"))
      (node (ref "C4") (pin "2") (pinfunction "2_2") (pintype "passive"))
      (node (ref "C40") (pin "-") (pinfunction "-_-") (pintype "passive"))
      (node (ref "C5") (pin "2") (pinfunction "2_2") (pintype "passive"))
      (node (ref "C6") (pin "-") (pinfunction "-_-") (pintype "passive"))
      (node (ref "C7") (pin "1") (pinfunction "1_1") (pintype "passive"))
      (node (ref "C8") (pin "1") (pinfunction "1_1") (pintype "passive"))
      (node (ref "C9") (pin "1") (pinfunction "1_1") (pintype "passive"))
      (node (ref "CAM") (pin "1") (pinfunction "S_1") (pintype "passive"))
      (node (ref "GND_IN") (pin "P$1") (pinfunction "P$1_P$1") (pintype "bidirectional"))
      (node (ref "GND_IN1") (pin "P$1") (pinfunction "P$1_P$1") (pintype "bidirectional"))
      (node (ref "GPS") (pin "1") (pinfunction "S_1") (pintype "passive"))
      (node (ref "IC1") (pin "2") (pinfunction "A1_2") (pintype "input"))
      (node (ref "IC1") (pin "3") (pinfunction "A2_3") (pintype "input"))
      (node (ref "IC1") (pin "4") (pinfunction "GND_4") (pintype "power_in"))
      (node (ref "IC1") (pin "7") (pinfunction "WP_7") (pintype "input"))
      (node (ref "IMU") (pin "1") (pinfunction "S_1") (pintype "passive"))
      (node (ref "IMU") (pin "2") (pinfunction "S_2") (pintype "passive"))
      (node (ref "LT_I2C") (pin "1") (pinfunction "GND_1") (pintype "bidirectional"))
      (node (ref "LT_I2C1") (pin "1") (pinfunction "GND_1") (pintype "bidirectional"))
      (node (ref "R14") (pin "1") (pinfunction "1_1") (pintype "passive"))
      (node (ref "R2") (pin "1") (pinfunction "1_1") (pintype "passive"))
      (node (ref "R3") (pin "1") (pinfunction "1_1") (pintype "passive"))
      (node (ref "R39") (pin "1") (pinfunction "1_1") (pintype "passive"))
      (node (ref "R42") (pin "1") (pinfunction "1_1") (pintype "passive"))
      (node (ref "R6") (pin "1") (pinfunction "1_1") (pintype "passive"))
      (node (ref "R8") (pin "2") (pinfunction "2_2") (pintype "passive"))
      (node (ref "RC") (pin "1") (pinfunction "S_1") (pintype "passive"))
      (node (ref "REG3V3D") (pin "2") (pinfunction "GND_2") (pintype "bidirectional"))
      (node (ref "REG3V3D") (pin "4") (pinfunction "TAB_4") (pintype "bidirectional"))
      (node (ref "REG5VA") (pin "2") (pinfunction "GND_2") (pintype "power_in"))
      (node (ref "REG5VD") (pin "P$2") (pinfunction "GND_P$2") (pintype "bidirectional"))
      (node (ref "SPI_0") (pin "1") (pinfunction "S_1") (pintype "passive"))
      (node (ref "U$1") (pin "18") (pinfunction "VSS_18") (pintype "power_in"))
      (node (ref "U$1") (pin "25") (pinfunction "VSS_25") (pintype "power_in"))
      (node (ref "U$1") (pin "42") (pinfunction "VSS_42") (pintype "power_in"))
      (node (ref "U$1") (pin "50") (pinfunction "VSS_50") (pintype "power_in"))
      (node (ref "U$1") (pin "59") (pinfunction "VSSA_59") (pintype "power_in"))
      (node (ref "U$1") (pin "6") (pinfunction "VSS_6") (pintype "power_in"))
      (node (ref "U$10") (pin "2") (pinfunction "A_2") (pintype "passive"))
      (node (ref "U$11") (pin "1") (pinfunction "GND_1") (pintype "bidirectional"))
      (node (ref "U$12") (pin "2") (pinfunction "GND_2") (pintype "bidirectional"))
      (node (ref "U$13") (pin "2") (pinfunction "GND_2") (pintype "bidirectional"))
      (node (ref "U$14") (pin "P$2") (pinfunction "S_P$2") (pintype "passive"))
      (node (ref "U$2") (pin "P$3") (pinfunction "GND_P$3") (pintype "bidirectional"))
      (node (ref "U$3") (pin "GND") (pinfunction "GND_GND") (pintype "passive"))
      (node (ref "U$5") (pin "4") (pinfunction "V-_4") (pintype "power_in"))
      (node (ref "U$5") (pin "6") (pinfunction "-IN_6") (pintype "input"))
      (node (ref "U$6") (pin "P$2") (pinfunction "S_P$2") (pintype "passive"))
      (node (ref "U$7") (pin "P$2") (pinfunction "S_P$2") (pintype "passive"))
      (node (ref "U$8") (pin "2") (pinfunction "GND_2") (pintype "bidirectional"))
      (node (ref "U$9") (pin "5") (pinfunction "IN-_5") (pintype "bidirectional"))
      (node (ref "U$9") (pin "8") (pinfunction "GND_8") (pintype "bidirectional"))
      (node (ref "U$9") (pin "9") (pinfunction "CA1_9") (pintype "bidirectional"))
      (node (ref "UART_0") (pin "1") (pinfunction "S_1") (pintype "passive"))
      (node (ref "UART_1") (pin "1") (pinfunction "S_1") (pintype "passive"))
      (node (ref "USB") (pin "5") (pinfunction "5_5") (pintype "input"))
    )
    (net (code "15") (name "LED_1") (class "Default")
      (node (ref "LED1") (pin "C") (pinfunction "C_C") (pintype "passive"))
      (node (ref "U$1") (pin "28") (pinfunction "P1.25(EXTIN0)_28") (pintype "bidirectional"))
    )
    (net (code "16") (name "LED_2") (class "Default")
      (node (ref "LED2") (pin "C") (pinfunction "C_C") (pintype "passive"))
      (node (ref "U$1") (pin "32") (pinfunction "P1.24(TRACECLK)_32") (pintype "bidirectional"))
    )
    (net (code "17") (name "LED_3") (class "Default")
      (node (ref "LED3") (pin "C") (pinfunction "C_C") (pintype "passive"))
      (node (ref "U$1") (pin "36") (pinfunction "P1.23(PIPESTAT2)_36") (pintype "bidirectional"))
    )
    (net (code "18") (name "LED_4") (class "Default")
      (node (ref "LED4") (pin "C") (pinfunction "C_C") (pintype "passive"))
      (node (ref "U$1") (pin "20") (pinfunction "P1.31(/TRST)_20") (pintype "bidirectional"))
    )
    (net (code "19") (name "LPC_RXD_0") (class "Default")
      (node (ref "GPS") (pin "4") (pinfunction "S_4") (pintype "passive"))
      (node (ref "U$1") (pin "21") (pinfunction "(RXD0/PWM3/EINT0)P0.1_21") (pintype "bidirectional"))
      (node (ref "UART_0") (pin "6") (pinfunction "S_6") (pintype "passive"))
    )
    (net (code "20") (name "LPC_RXD_1") (class "Default")
      (node (ref "U$1") (pin "34") (pinfunction "(RXD1/PWM6/EINT3)P0.9_34") (pintype "bidirectional"))
      (node (ref "U$8") (pin "1") (pinfunction "B2_1") (pintype "bidirectional"))
    )
    (net (code "21") (name "LPC_TXD_0") (class "Default")
      (node (ref "GPS") (pin "5") (pinfunction "S_5") (pintype "passive"))
      (node (ref "U$1") (pin "19") (pinfunction "(TXD0/PWM1)P0.0_19") (pintype "bidirectional"))
      (node (ref "UART_0") (pin "5") (pinfunction "S_5") (pintype "passive"))
    )
    (net (code "22") (name "LPC_TXD_1") (class "Default")
      (node (ref "U$1") (pin "33") (pinfunction "(TXD1/PWM4/AD1.1)P0.8_33") (pintype "bidirectional"))
      (node (ref "U$8") (pin "8") (pinfunction "B1_8") (pintype "bidirectional"))
    )
    (net (code "23") (name "LT_I2C_1_SCL") (class "Default")
      (node (ref "LT_I2C") (pin "6") (pinfunction "SCL2_6") (pintype "bidirectional"))
      (node (ref "R44") (pin "1") (pinfunction "1_1") (pintype "passive"))
      (node (ref "UART_0") (pin "3") (pinfunction "S_3") (pintype "passive"))
    )
    (net (code "24") (name "LT_I2C_1_SDA") (class "Default")
      (node (ref "LT_I2C") (pin "5") (pinfunction "SDA2_5") (pintype "bidirectional"))
      (node (ref "R43") (pin "1") (pinfunction "1_1") (pintype "passive"))
      (node (ref "UART_0") (pin "4") (pinfunction "S_4") (pintype "passive"))
    )
    (net (code "25") (name "LT_I2C_1_SUP") (class "Default")
      (node (ref "R25") (pin "2") (pinfunction "2_2") (pintype "passive"))
      (node (ref "R26") (pin "2") (pinfunction "2_2") (pintype "passive"))
      (node (ref "R27") (pin "2") (pinfunction "2_2") (pintype "passive"))
      (node (ref "R43") (pin "2") (pinfunction "2_2") (pintype "passive"))
      (node (ref "R44") (pin "2") (pinfunction "2_2") (pintype "passive"))
      (node (ref "UART_0") (pin "2") (pinfunction "S_2") (pintype "passive"))
    )
    (net (code "26") (name "LT_UART1_LPC_RX") (class "Default")
      (node (ref "U$8") (pin "4") (pinfunction "A2_4") (pintype "bidirectional"))
      (node (ref "UART_1") (pin "4") (pinfunction "S_4") (pintype "passive"))
    )
    (net (code "27") (name "LT_UART1_LPC_TX") (class "Default")
      (node (ref "U$8") (pin "5") (pinfunction "A1_5") (pintype "bidirectional"))
      (node (ref "UART_1") (pin "5") (pinfunction "S_5") (pintype "passive"))
    )
    (net (code "28") (name "LT_UART1_SUP") (class "Default")
      (node (ref "C23") (pin "1") (pinfunction "1_1") (pintype "passive"))
      (node (ref "R23") (pin "2") (pinfunction "2_2") (pintype "passive"))
      (node (ref "R24") (pin "2") (pinfunction "2_2") (pintype "passive"))
      (node (ref "UART_1") (pin "3") (pinfunction "S_3") (pintype "passive"))
    )
    (net (code "29") (name "MAG_RESET") (class "Default")
      (node (ref "IMU") (pin "11") (pinfunction "S_11") (pintype "passive"))
      (node (ref "U$1") (pin "4") (pinfunction "P1.19(TRACEPKT3)_4") (pintype "bidirectional"))
    )
    (net (code "30") (name "MATCH0") (class "Default")
      (node (ref "CAM") (pin "6") (pinfunction "S_6") (pintype "passive"))
      (node (ref "U$1") (pin "2") (pinfunction "(AD1.7/CAP0.0/MAT0.0)P0.22_2") (pintype "bidirectional"))
    )
    (net (code "31") (name "MISO_0") (class "Default")
      (node (ref "SPI_0") (pin "6") (pinfunction "S_6") (pintype "passive"))
      (node (ref "U$1") (pin "29") (pinfunction "(MISO0/MAT0.1/A0.7)P0.5_29") (pintype "bidirectional"))
    )
    (net (code "32") (name "MISO_1") (class "Default")
      (node (ref "IMU") (pin "5") (pinfunction "S_5") (pintype "passive"))
      (node (ref "U$1") (pin "53") (pinfunction "(CAP1.3/MISO1/MAT1.3)P0.18_53") (pintype "bidirectional"))
    )
    (net (code "33") (name "MOSI_0") (class "Default")
      (node (ref "SPI_0") (pin "5") (pinfunction "S_5") (pintype "passive"))
      (node (ref "U$1") (pin "30") (pinfunction "(MOSI0/CAP0.2/AD1.0)P0.6_30") (pintype "bidirectional"))
    )
    (net (code "34") (name "MOSI_1") (class "Default")
      (node (ref "IMU") (pin "4") (pinfunction "S_4") (pintype "passive"))
      (node (ref "U$1") (pin "54") (pinfunction "(MAT1.2/MOSI1/CAP1.2)P0.19_54") (pintype "bidirectional"))
    )
    (net (code "35") (name "NC_1") (class "Default")
      (node (ref "U$1") (pin "38") (pinfunction "(DSR1/MAT1.0/AD1.3)P0.12_38") (pintype "bidirectional"))
    )
    (net (code "36") (name "NC_7") (class "Default")
      (node (ref "U$1") (pin "56") (pinfunction "P1.29(TCK)_56") (pintype "bidirectional"))
    )
    (net (code "37") (name "NC_8") (class "Default")
      (node (ref "U$1") (pin "52") (pinfunction "P1.30(TMS)_52") (pintype "bidirectional"))
    )
    (net (code "38") (name "NC_10") (class "Default")
      (node (ref "U$1") (pin "3") (pinfunction "RTXC1_3") (pintype "input"))
    )
    (net (code "39") (name "NC_11") (class "Default")
      (node (ref "U$1") (pin "5") (pinfunction "RTXC2_5") (pintype "output"))
    )
    (net (code "40") (name "Net-(C26-Pad1)") (class "Default")
      (node (ref "C26") (pin "1") (pinfunction "1_1") (pintype "passive"))
      (node (ref "R20") (pin "1") (pinfunction "1_1") (pintype "passive"))
      (node (ref "R21") (pin "2") (pinfunction "2_2") (pintype "passive"))
    )
    (net (code "41") (name "Net-(IC1-A0)") (class "Default")
      (node (ref "IC1") (pin "1") (pinfunction "A0_1") (pintype "input"))
      (node (ref "R41") (pin "2") (pinfunction "2_2") (pintype "passive"))
      (node (ref "R42") (pin "2") (pinfunction "2_2") (pintype "passive"))
    )
    (net (code "42") (name "Net-(LED1-PadA)") (class "Default")
      (node (ref "LED1") (pin "A") (pinfunction "A_A") (pintype "passive"))
      (node (ref "R13") (pin "1") (pinfunction "1_1") (pintype "passive"))
    )
    (net (code "43") (name "Net-(LED2-PadA)") (class "Default")
      (node (ref "LED2") (pin "A") (pinfunction "A_A") (pintype "passive"))
      (node (ref "R15") (pin "1") (pinfunction "1_1") (pintype "passive"))
    )
    (net (code "44") (name "Net-(LED3-PadA)") (class "Default")
      (node (ref "LED3") (pin "A") (pinfunction "A_A") (pintype "passive"))
      (node (ref "R16") (pin "1") (pinfunction "1_1") (pintype "passive"))
    )
    (net (code "45") (name "Net-(LED4-PadA)") (class "Default")
      (node (ref "LED4") (pin "A") (pinfunction "A_A") (pintype "passive"))
      (node (ref "R22") (pin "1") (pinfunction "1_1") (pintype "passive"))
    )
    (net (code "46") (name "Net-(LT_I2C-EN)") (class "Default")
      (node (ref "LT_I2C") (pin "7") (pinfunction "VREF2_7") (pintype "bidirectional"))
      (node (ref "LT_I2C") (pin "8") (pinfunction "EN_8") (pintype "bidirectional"))
      (node (ref "R25") (pin "1") (pinfunction "1_1") (pintype "passive"))
    )
    (net (code "47") (name "Net-(LT_I2C1-EN)") (class "Default")
      (node (ref "LT_I2C1") (pin "7") (pinfunction "VREF2_7") (pintype "bidirectional"))
      (node (ref "LT_I2C1") (pin "8") (pinfunction "EN_8") (pintype "bidirectional"))
      (node (ref "R47") (pin "1") (pinfunction "1_1") (pintype "passive"))
    )
    (net (code "48") (name "Net-(MC1A-S)") (class "Default")
      (node (ref "MC1") (pin "1") (pinfunction "S_1") (pintype "passive"))
      (node (ref "MC2") (pin "1") (pinfunction "S_1") (pintype "passive"))
      (node (ref "MC3") (pin "1") (pinfunction "S_1") (pintype "passive"))
      (node (ref "MC4") (pin "1") (pinfunction "S_1") (pintype "passive"))
      (node (ref "R46") (pin "2") (pinfunction "2_2") (pintype "passive"))
      (node (ref "U$11") (pin "5") (pinfunction "SDA2_5") (pintype "bidirectional"))
    )
    (net (code "49") (name "Net-(MC1B-S)") (class "Default")
      (node (ref "MC1") (pin "2") (pinfunction "S_2") (pintype "passive"))
      (node (ref "MC2") (pin "2") (pinfunction "S_2") (pintype "passive"))
      (node (ref "MC3") (pin "2") (pinfunction "S_2") (pintype "passive"))
      (node (ref "MC4") (pin "2") (pinfunction "S_2") (pintype "passive"))
      (node (ref "R45") (pin "2") (pinfunction "2_2") (pintype "passive"))
      (node (ref "U$11") (pin "6") (pinfunction "SCL2_6") (pintype "bidirectional"))
    )
    (net (code "50") (name "Net-(PSA-S)") (class "Default")
      (node (ref "PS") (pin "1") (pinfunction "S_1") (pintype "passive"))
      (node (ref "U$3") (pin "P$2") (pinfunction "S_P$2") (pintype "passive"))
    )
    (net (code "51") (name "Net-(PSB-S)") (class "Default")
      (node (ref "PS") (pin "2") (pinfunction "S_2") (pintype "passive"))
      (node (ref "U$3") (pin "P$1") (pinfunction "P_P$1") (pintype "passive"))
    )
    (net (code "52") (name "Net-(Q1-PadC)") (class "Default")
      (node (ref "Q1") (pin "C") (pinfunction "C_C") (pintype "passive"))
      (node (ref "R19") (pin "2") (pinfunction "2_2") (pintype "passive"))
    )
    (net (code "53") (name "Net-(R30-Pad1)") (class "Default")
      (node (ref "R30") (pin "1") (pinfunction "1_1") (pintype "passive"))
      (node (ref "R31") (pin "2") (pinfunction "2_2") (pintype "passive"))
      (node (ref "R32") (pin "2") (pinfunction "2_2") (pintype "passive"))
    )
    (net (code "54") (name "Net-(RCC-S)") (class "Default")
      (node (ref "R12") (pin "2") (pinfunction "2_2") (pintype "passive"))
      (node (ref "RC") (pin "3") (pinfunction "S_3") (pintype "passive"))
    )
    (net (code "55") (name "Net-(REG5VA-ADJ)") (class "Default")
      (node (ref "C19") (pin "1") (pinfunction "1_1") (pintype "passive"))
      (node (ref "REG5VA") (pin "4") (pinfunction "ADJ_4") (pintype "passive"))
    )
    (net (code "56") (name "Net-(REG5VD-ADJ)") (class "Default")
      (node (ref "R14") (pin "2") (pinfunction "2_2") (pintype "passive"))
      (node (ref "REG5VD") (pin "P$4") (pinfunction "ADJ_P$4") (pintype "bidirectional"))
    )
    (net (code "57") (name "Net-(REG6V5A-ADJ)") (class "Default")
      (node (ref "R3") (pin "2") (pinfunction "2_2") (pintype "passive"))
      (node (ref "R4") (pin "1") (pinfunction "1_1") (pintype "passive"))
      (node (ref "REG6V5A") (pin "1") (pinfunction "ADJ_1") (pintype "input"))
    )
    (net (code "58") (name "Net-(U$1-RESET)") (class "Default")
      (node (ref "C9") (pin "2") (pinfunction "2_2") (pintype "passive"))
      (node (ref "R7") (pin "1") (pinfunction "1_1") (pintype "passive"))
      (node (ref "U$1") (pin "57") (pinfunction "RESET_57") (pintype "input"))
    )
    (net (code "59") (name "Net-(U$1-XTAL1)") (class "Default")
      (node (ref "C7") (pin "2") (pinfunction "2_2") (pintype "passive"))
      (node (ref "U$1") (pin "62") (pinfunction "XTAL1_62") (pintype "input"))
      (node (ref "U$4") (pin "P$1") (pinfunction "P$1_P$1") (pintype "bidirectional"))
    )
    (net (code "60") (name "Net-(U$1-XTAL2)") (class "Default")
      (node (ref "C8") (pin "2") (pinfunction "2_2") (pintype "passive"))
      (node (ref "U$1") (pin "61") (pinfunction "XTAL2_61") (pintype "output"))
      (node (ref "U$4") (pin "P$3") (pinfunction "P$2_P$3") (pintype "bidirectional"))
    )
    (net (code "61") (name "Net-(U$2-VO)") (class "Default")
      (node (ref "U$2") (pin "P$4") (pinfunction "VO_P$4") (pintype "bidirectional"))
      (node (ref "U$5") (pin "3") (pinfunction "+IN_3") (pintype "input"))
      (node (ref "U$9") (pin "4") (pinfunction "IN+_4") (pintype "bidirectional"))
    )
    (net (code "62") (name "Net-(U$5A--IN)") (class "Default")
      (node (ref "C24") (pin "2") (pinfunction "2_2") (pintype "passive"))
      (node (ref "R10") (pin "1") (pinfunction "1_1") (pintype "passive"))
      (node (ref "R20") (pin "2") (pinfunction "2_2") (pintype "passive"))
      (node (ref "R5") (pin "2") (pinfunction "2_2") (pintype "passive"))
      (node (ref "R6") (pin "2") (pinfunction "2_2") (pintype "passive"))
      (node (ref "U$5") (pin "2") (pinfunction "-IN_2") (pintype "input"))
    )
    (net (code "63") (name "Net-(U$5A-OUT)") (class "Default")
      (node (ref "C24") (pin "1") (pinfunction "1_1") (pintype "passive"))
      (node (ref "R10") (pin "2") (pinfunction "2_2") (pintype "passive"))
      (node (ref "R11") (pin "1") (pinfunction "1_1") (pintype "passive"))
      (node (ref "U$5") (pin "1") (pinfunction "OUT_1") (pintype "output"))
    )
    (net (code "64") (name "Net-(U$8-OE)") (class "Default")
      (node (ref "R23") (pin "1") (pinfunction "1_1") (pintype "passive"))
      (node (ref "U$8") (pin "3") (pinfunction "VCCA_3") (pintype "bidirectional"))
      (node (ref "U$8") (pin "6") (pinfunction "OE_6") (pintype "bidirectional"))
    )
    (net (code "65") (name "Net-(U$10-C)") (class "Default")
      (node (ref "R38") (pin "1") (pinfunction "1_1") (pintype "passive"))
      (node (ref "R40") (pin "2") (pinfunction "2_2") (pintype "passive"))
      (node (ref "U$10") (pin "3") (pinfunction "C_3") (pintype "passive"))
      (node (ref "U$9") (pin "3") (pinfunction "REF-_3") (pintype "bidirectional"))
    )
    (net (code "66") (name "Net-(U$10-R)") (class "Default")
      (node (ref "R39") (pin "2") (pinfunction "2_2") (pintype "passive"))
      (node (ref "R40") (pin "1") (pinfunction "1_1") (pintype "passive"))
      (node (ref "U$10") (pin "5") (pinfunction "R_5") (pintype "passive"))
    )
    (net (code "67") (name "Net-(U$11-EN)") (class "Default")
      (node (ref "R30") (pin "2") (pinfunction "2_2") (pintype "passive"))
      (node (ref "U$11") (pin "7") (pinfunction "VREF2_7") (pintype "bidirectional"))
      (node (ref "U$11") (pin "8") (pinfunction "EN_8") (pintype "bidirectional"))
    )
    (net (code "68") (name "OFFSET") (class "Default")
      (node (ref "R21") (pin "1") (pinfunction "1_1") (pintype "passive"))
      (node (ref "U$1") (pin "9") (pinfunction "(AD0.4/AOUT)P0.25_9") (pintype "bidirectional"))
    )
    (net (code "69") (name "PB1_INT") (class "Default")
      (node (ref "R35") (pin "1") (pinfunction "1_1") (pintype "passive"))
      (node (ref "R48") (pin "1") (pinfunction "1_1") (pintype "passive"))
      (node (ref "U$1") (pin "45") (pinfunction "(RI1/EINT2/AD1.5)P0.15_45") (pintype "bidirectional"))
      (node (ref "U$6") (pin "P$1") (pinfunction "P_P$1") (pintype "passive"))
    )
    (net (code "70") (name "PB2") (class "Default")
      (node (ref "R36") (pin "1") (pinfunction "1_1") (pintype "passive"))
      (node (ref "U$1") (pin "48") (pinfunction "P1.20(TRACESYNC)_48") (pintype "bidirectional"))
      (node (ref "U$7") (pin "P$1") (pinfunction "P_P$1") (pintype "passive"))
    )
    (net (code "71") (name "PB3") (class "Default")
      (node (ref "R37") (pin "1") (pinfunction "1_1") (pintype "passive"))
      (node (ref "U$1") (pin "44") (pinfunction "P1.21(PIPESTAT0)_44") (pintype "bidirectional"))
      (node (ref "U$14") (pin "P$1") (pinfunction "P_P$1") (pintype "passive"))
    )
    (net (code "72") (name "PPM_IN") (class "Default")
      (node (ref "R12") (pin "1") (pinfunction "1_1") (pintype "passive"))
      (node (ref "U$1") (pin "13") (pinfunction "(AD0.1/CAP0.2/MAT0.2)P0.28_13") (pintype "bidirectional"))
    )
    (net (code "73") (name "PPS") (class "Default")
      (node (ref "GPS") (pin "8") (pinfunction "S_8") (pintype "passive"))
      (node (ref "R48") (pin "2") (pinfunction "2_2") (pintype "passive"))
    )
    (net (code "74") (name "PRESSURE") (class "Default")
      (node (ref "C25") (pin "1") (pinfunction "1_1") (pintype "passive"))
      (node (ref "R11") (pin "2") (pinfunction "2_2") (pintype "passive"))
      (node (ref "U$1") (pin "35") (pinfunction "(RTS1/CAP1.0/AD1.2)P0.10_35") (pintype "bidirectional"))
    )
    (net (code "75") (name "PSW_1") (class "Default")
      (node (ref "C39") (pin "1") (pinfunction "1_1") (pintype "passive"))
      (node (ref "C40") (pin "+") (pinfunction "+_+") (pintype "passive"))
      (node (ref "CAM") (pin "3") (pinfunction "S_3") (pintype "passive"))
      (node (ref "U$13") (pin "1") (pinfunction "OUT_1") (pintype "bidirectional"))
    )
    (net (code "76") (name "PSW_2") (class "Default")
      (node (ref "C37") (pin "1") (pinfunction "1_1") (pintype "passive"))
      (node (ref "C38") (pin "+") (pinfunction "+_+") (pintype "passive"))
      (node (ref "CAM") (pin "4") (pinfunction "S_4") (pintype "passive"))
      (node (ref "U$12") (pin "1") (pinfunction "OUT_1") (pintype "bidirectional"))
    )
    (net (code "77") (name "PWM5") (class "Default")
      (node (ref "CAM") (pin "5") (pinfunction "S_5") (pintype "passive"))
      (node (ref "U$1") (pin "1") (pinfunction "(PWM5/AD1.6/CAP1.3)P0.21_1") (pintype "bidirectional"))
    )
    (net (code "78") (name "PWR_SW") (class "Default")
      (node (ref "U$1") (pin "8") (pinfunction "P1.18(TRACEPKT2)_8") (pintype "bidirectional"))
      (node (ref "U$12") (pin "4") (pinfunction "EN_4") (pintype "bidirectional"))
    )
    (net (code "79") (name "SCK_0") (class "Default")
      (node (ref "SPI_0") (pin "7") (pinfunction "S_7") (pintype "passive"))
      (node (ref "U$1") (pin "27") (pinfunction "(SCK0/CAP0.1/AD0.6)P0.4_27") (pintype "bidirectional"))
    )
    (net (code "80") (name "SCK_1") (class "Default")
      (node (ref "IMU") (pin "6") (pinfunction "S_6") (pintype "passive"))
      (node (ref "U$1") (pin "47") (pinfunction "(CAP1.2/SCK1/MAT1.2)P0.17_47") (pintype "bidirectional"))
    )
    (net (code "81") (name "SCL_0") (class "Default")
      (node (ref "R29") (pin "2") (pinfunction "2_2") (pintype "passive"))
      (node (ref "U$1") (pin "22") (pinfunction "(SCL0/CAP0.0)P0.2_22") (pintype "bidirectional"))
      (node (ref "U$11") (pin "3") (pinfunction "SCL1_3") (pintype "bidirectional"))
    )
    (net (code "82") (name "SCL_1") (class "Default")
      (node (ref "GPS") (pin "6") (pinfunction "S_6") (pintype "passive"))
      (node (ref "IC1") (pin "6") (pinfunction "SCL_6") (pintype "input"))
      (node (ref "LT_I2C") (pin "3") (pinfunction "SCL1_3") (pintype "bidirectional"))
      (node (ref "LT_I2C1") (pin "3") (pinfunction "SCL1_3") (pintype "bidirectional"))
      (node (ref "R33") (pin "1") (pinfunction "1_1") (pintype "passive"))
      (node (ref "U$1") (pin "37") (pinfunction "(CTS1/CAP1.1/SCL1)P0.11_37") (pintype "bidirectional"))
    )
    (net (code "83") (name "SDA_0") (class "Default")
      (node (ref "R28") (pin "2") (pinfunction "2_2") (pintype "passive"))
      (node (ref "U$1") (pin "26") (pinfunction "(SDA0/MAT0.0/EINT1)P0.3_26") (pintype "bidirectional"))
      (node (ref "U$11") (pin "4") (pinfunction "SDA1_4") (pintype "bidirectional"))
    )
    (net (code "84") (name "SSEL_0") (class "Default")
      (node (ref "SPI_0") (pin "4") (pinfunction "S_4") (pintype "passive"))
      (node (ref "U$1") (pin "31") (pinfunction "(SSEL0/PWM2/EINT2)P0.7_31") (pintype "bidirectional"))
    )
    (net (code "85") (name "SSEL_1") (class "Default")
      (node (ref "IMU") (pin "7") (pinfunction "S_7") (pintype "passive"))
      (node (ref "U$1") (pin "55") (pinfunction "(MAT1.3/SSEL1/EINT3)P0.20_55") (pintype "bidirectional"))
    )
    (net (code "86") (name "SSEL_2") (class "Default")
      (node (ref "IMU") (pin "8") (pinfunction "S_8") (pintype "passive"))
      (node (ref "U$1") (pin "60") (pinfunction "P1.28(TDI)_60") (pintype "bidirectional"))
    )
    (net (code "87") (name "SSEL_EEP") (class "Default")
      (node (ref "IMU") (pin "12") (pinfunction "S_12") (pintype "passive"))
      (node (ref "U$1") (pin "64") (pinfunction "P1.27(TDO)_64") (pintype "bidirectional"))
    )
    (net (code "88") (name "USB+") (class "Default")
      (node (ref "R17") (pin "2") (pinfunction "2_2") (pintype "passive"))
      (node (ref "USB") (pin "3") (pinfunction "3_3") (pintype "input"))
    )
    (net (code "89") (name "USB-") (class "Default")
      (node (ref "R18") (pin "2") (pinfunction "2_2") (pintype "passive"))
      (node (ref "USB") (pin "2") (pinfunction "2_2") (pintype "input"))
    )
    (net (code "90") (name "USB_CONNECT") (class "Default")
      (node (ref "Q1") (pin "B") (pinfunction "B_B") (pintype "passive"))
      (node (ref "U$1") (pin "17") (pinfunction "(UP_LED/CONNECT)P0.31_17") (pintype "output"))
    )
    (net (code "91") (name "USB_N") (class "Default")
      (node (ref "C28") (pin "1") (pinfunction "1_1") (pintype "passive"))
      (node (ref "R18") (pin "1") (pinfunction "1_1") (pintype "passive"))
      (node (ref "U$1") (pin "11") (pinfunction "D-_11") (pintype "bidirectional"))
    )
    (net (code "92") (name "USB_P") (class "Default")
      (node (ref "C29") (pin "1") (pinfunction "1_1") (pintype "passive"))
      (node (ref "R17") (pin "1") (pinfunction "1_1") (pintype "passive"))
      (node (ref "R19") (pin "1") (pinfunction "1_1") (pintype "passive"))
      (node (ref "U$1") (pin "10") (pinfunction "D+_10") (pintype "bidirectional"))
    )
    (net (code "93") (name "USB_VBUS") (class "Default")
      (node (ref "R9") (pin "1") (pinfunction "1_1") (pintype "passive"))
      (node (ref "USB") (pin "1") (pinfunction "1_1") (pintype "input"))
    )
    (net (code "94") (name "USB_VBUS_3V3") (class "Default")
      (node (ref "R8") (pin "1") (pinfunction "1_1") (pintype "passive"))
      (node (ref "R9") (pin "2") (pinfunction "2_2") (pintype "passive"))
      (node (ref "U$1") (pin "58") (pinfunction "(VBUS)P0.23_58") (pintype "bidirectional"))
    )
    (net (code "95") (name "VBAT_MEAS") (class "Default")
      (node (ref "R1") (pin "1") (pinfunction "1_1") (pintype "passive"))
      (node (ref "R2") (pin "2") (pinfunction "2_2") (pintype "passive"))
      (node (ref "U$1") (pin "14") (pinfunction "(AD0.2/CAP0.3/MAT0.3)P0.29_14") (pintype "bidirectional"))
    )
    (net (code "96") (name "unconnected-(REG5VD-IHN-PadP$5)") (class "Default")
      (node (ref "REG5VD") (pin "P$5") (pinfunction "IHN_P$5") (pintype "bidirectional"))
    )
    (net (code "97") (name "unconnected-(U$1-P1.16(TRACEPKT0)-Pad16)") (class "Default")
      (node (ref "U$1") (pin "16") (pinfunction "P1.16(TRACEPKT0)_16") (pintype "bidirectional"))
    )
    (net (code "98") (name "unconnected-(U$1-P1.17(TRACEPKT1)-Pad12)") (class "Default")
      (node (ref "U$1") (pin "12") (pinfunction "P1.17(TRACEPKT1)_12") (pintype "bidirectional"))
    )
    (net (code "99") (name "unconnected-(U$5B-OUT-Pad7)") (class "Default")
      (node (ref "U$5") (pin "7") (pinfunction "OUT_7") (pintype "output"))
    )
    (net (code "100") (name "unconnected-(U$9-CA0{slash}F0-Pad10)") (class "Default")
      (node (ref "U$9") (pin "10") (pinfunction "CA0/F0_10") (pintype "bidirectional"))
    )
    (net (code "101") (name "unconnected-(U$12-OC-Pad3)") (class "Default")
      (node (ref "U$12") (pin "3") (pinfunction "OC_3") (pintype "bidirectional"))
    )
    (net (code "102") (name "unconnected-(U$13-OC-Pad3)") (class "Default")
      (node (ref "U$13") (pin "3") (pinfunction "OC_3") (pintype "bidirectional"))
    )
    (net (code "103") (name "unconnected-(USB-Pad4)") (class "Default")
      (node (ref "USB") (pin "4") (pinfunction "4_4") (pintype "input"))
    )
  )
)
